# main.net
KiCad netlist of a schematic drawn in EAGLE
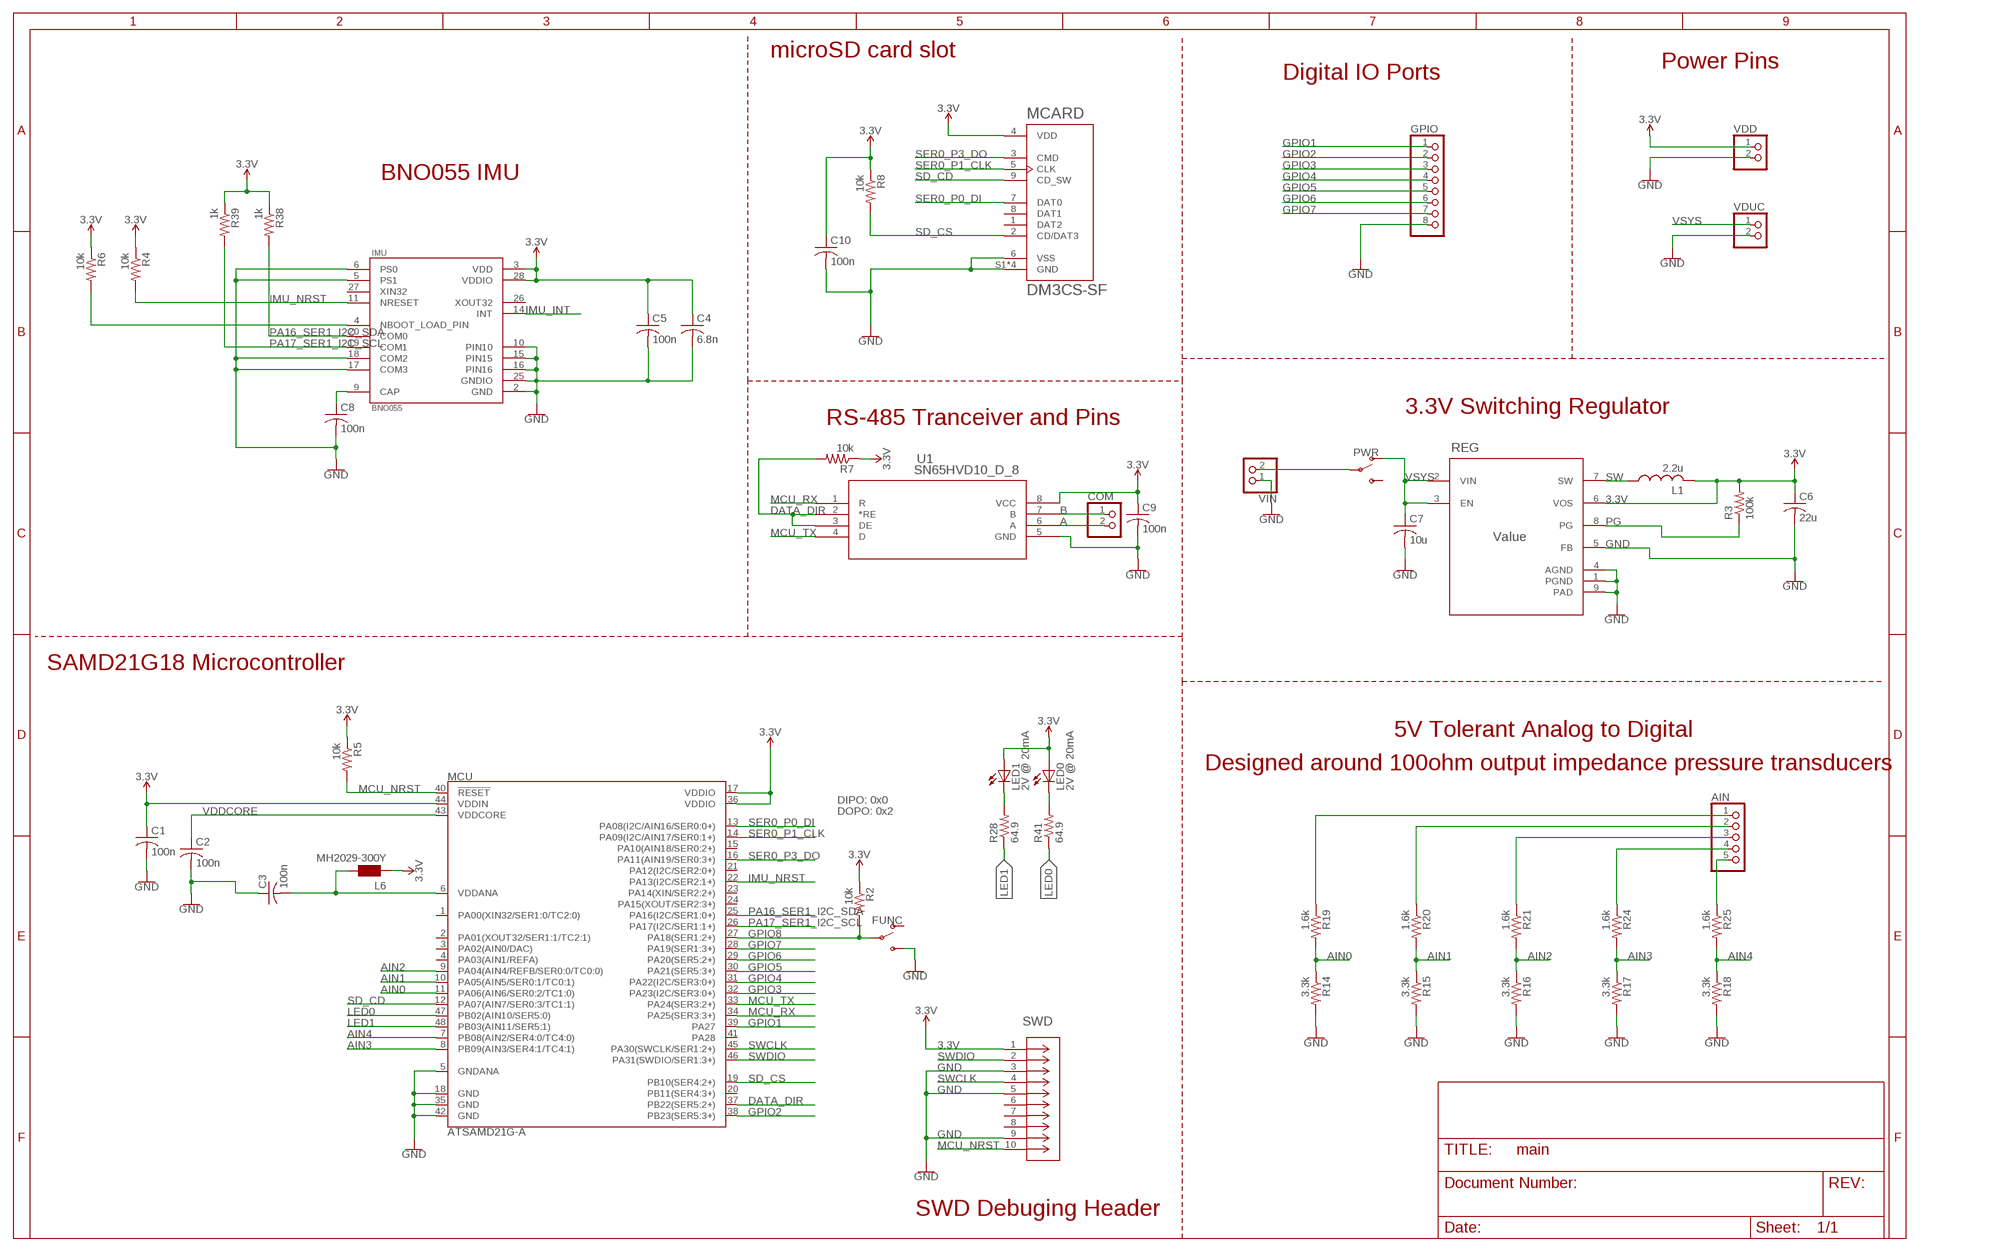
[diagram p0: schematic, sheet 1]

(export (version "E")
  (design (tool "Eeschema 10.0.6"))
  (components
    (comp (ref "AIN")
      (value "PINHD-1X5")
      (footprint "eagle-import:1X05")
      (libsource (lib "eagle-import") (part "PINHD-1X5"))
    )
    (comp (ref "C1")
      (value "100n")
      (footprint "eagle-import:C0603")
      (libsource (lib "eagle-import") (part "C-USC0603"))
    )
    (comp (ref "C2")
      (value "100n")
      (footprint "eagle-import:C0603")
      (libsource (lib "eagle-import") (part "C-USC0603"))
    )
    (comp (ref "C3")
      (value "100n")
      (footprint "eagle-import:C0603")
      (libsource (lib "eagle-import") (part "C-USC0603"))
    )
    (comp (ref "C4")
      (value "6.8n")
      (footprint "eagle-import:C0603")
      (libsource (lib "eagle-import") (part "C-USC0603"))
    )
    (comp (ref "C5")
      (value "100n")
      (footprint "eagle-import:C0603")
      (libsource (lib "eagle-import") (part "C-USC0603"))
    )
    (comp (ref "C6")
      (value "22u")
      (footprint "eagle-import:C0603")
      (libsource (lib "eagle-import") (part "C-USC0603"))
    )
    (comp (ref "C7")
      (value "10u")
      (footprint "eagle-import:C0603")
      (libsource (lib "eagle-import") (part "C-USC0603"))
    )
    (comp (ref "C8")
      (value "100n")
      (footprint "eagle-import:C0603")
      (libsource (lib "eagle-import") (part "C-USC0603"))
    )
    (comp (ref "C9")
      (value "100n")
      (footprint "eagle-import:C0603")
      (libsource (lib "eagle-import") (part "C-USC0603"))
    )
    (comp (ref "C10")
      (value "100n")
      (footprint "eagle-import:C0603")
      (libsource (lib "eagle-import") (part "C-USC0603"))
    )
    (comp (ref "COM")
      (value "PINHD-1X2")
      (footprint "eagle-import:1X02")
      (libsource (lib "eagle-import") (part "PINHD-1X2"))
    )
    (comp (ref "FUNC")
      (value "SWITCH-SPDT-SMD-AYZ0202")
      (footprint "eagle-import:SWITCH_DPDT_SMD_AYZ0202")
      (libsource (lib "eagle-import") (part "SWITCH-SPDT-SMD-AYZ0202"))
    )
    (comp (ref "GPIO")
      (value "PINHD-1X8")
      (footprint "eagle-import:1X08")
      (libsource (lib "eagle-import") (part "PINHD-1X8"))
    )
    (comp (ref "IMU")
      (value "BNO055")
      (footprint "eagle-import:LGA28R50P4X10_380X520X100")
      (fields (field (name "MF") "Bosch"))
      (libsource (lib "eagle-import") (part "BNO055"))
    )
    (comp (ref "L1")
      (value "2.2u")
      (footprint "eagle-import:L2012C")
      (libsource (lib "eagle-import") (part "L-USL2012C"))
    )
    (comp (ref "L6")
      (value "MH2029-300Y")
      (footprint "eagle-import:0805")
      (fields (field (name "PART_NUMBER") "BLM21PG300SN1D_/_MH2029-300Y"))
      (libsource (lib "eagle-import") (part "0001_BLM21PG300SN1D_/_MH2029-300Y"))
    )
    (comp (ref "LED0")
      (value "2V @ 20mA")
      (footprint "eagle-import:CHIPLED_0603")
      (libsource (lib "eagle-import") (part "LEDCHIPLED_0603"))
    )
    (comp (ref "LED1")
      (value "2V @ 20mA")
      (footprint "eagle-import:CHIPLED_0603")
      (libsource (lib "eagle-import") (part "LEDCHIPLED_0603"))
    )
    (comp (ref "MCARD")
      (value "DM3CS-SF")
      (footprint "eagle-import:HRS_DM3CS-SF")
      (fields (field (name "DIGI-KEY_PART_NUMBER") "HR1972CT-ND") (field (name "MF") "Hirose"))
      (libsource (lib "eagle-import") (part "DM3CS-SF"))
    )
    (comp (ref "MCU")
      (value "ATSAMD21G-A")
      (footprint "eagle-import:TQFP-48")
      (libsource (lib "eagle-import") (part "ATSAMD21G-A"))
    )
    (comp (ref "PWR")
      (value "SWITCH-SPDT-PTH-11.6X4.0MM")
      (footprint "eagle-import:SWITCH_SPDT_PTH_11.6X4.0MM")
      (libsource (lib "eagle-import") (part "SWITCH-SPDT-PTH-11.6X4.0MM"))
    )
    (comp (ref "R2")
      (value "10k")
      (footprint "eagle-import:R0603")
      (libsource (lib "eagle-import") (part "R-US_R0603"))
    )
    (comp (ref "R3")
      (value "100k")
      (footprint "eagle-import:R0603")
      (libsource (lib "eagle-import") (part "R-US_R0603"))
    )
    (comp (ref "R4")
      (value "10k")
      (footprint "eagle-import:R0603")
      (libsource (lib "eagle-import") (part "R-US_R0603"))
    )
    (comp (ref "R5")
      (value "10k")
      (footprint "eagle-import:R0603")
      (libsource (lib "eagle-import") (part "R-US_R0603"))
    )
    (comp (ref "R6")
      (value "10k")
      (footprint "eagle-import:R0603")
      (libsource (lib "eagle-import") (part "R-US_R0603"))
    )
    (comp (ref "R7")
      (value "10k")
      (footprint "eagle-import:R0603")
      (libsource (lib "eagle-import") (part "R-US_R0603"))
    )
    (comp (ref "R8")
      (value "10k")
      (footprint "eagle-import:R0603")
      (libsource (lib "eagle-import") (part "R-US_R0603"))
    )
    (comp (ref "R14")
      (value "3.3k")
      (footprint "eagle-import:R0603")
      (libsource (lib "eagle-import") (part "R-US_R0603"))
    )
    (comp (ref "R15")
      (value "3.3k")
      (footprint "eagle-import:R0603")
      (libsource (lib "eagle-import") (part "R-US_R0603"))
    )
    (comp (ref "R16")
      (value "3.3k")
      (footprint "eagle-import:R0603")
      (libsource (lib "eagle-import") (part "R-US_R0603"))
    )
    (comp (ref "R17")
      (value "3.3k")
      (footprint "eagle-import:R0603")
      (libsource (lib "eagle-import") (part "R-US_R0603"))
    )
    (comp (ref "R18")
      (value "3.3k")
      (footprint "eagle-import:R0603")
      (libsource (lib "eagle-import") (part "R-US_R0603"))
    )
    (comp (ref "R19")
      (value "1.6k")
      (footprint "eagle-import:R0603")
      (libsource (lib "eagle-import") (part "R-US_R0603"))
    )
    (comp (ref "R20")
      (value "1.6k")
      (footprint "eagle-import:R0603")
      (libsource (lib "eagle-import") (part "R-US_R0603"))
    )
    (comp (ref "R21")
      (value "1.6k")
      (footprint "eagle-import:R0603")
      (libsource (lib "eagle-import") (part "R-US_R0603"))
    )
    (comp (ref "R24")
      (value "1.6k")
      (footprint "eagle-import:R0603")
      (libsource (lib "eagle-import") (part "R-US_R0603"))
    )
    (comp (ref "R25")
      (value "1.6k")
      (footprint "eagle-import:R0603")
      (libsource (lib "eagle-import") (part "R-US_R0603"))
    )
    (comp (ref "R28")
      (value "64.9")
      (footprint "eagle-import:R0603")
      (libsource (lib "eagle-import") (part "R-US_R0603"))
    )
    (comp (ref "R38")
      (value "1k")
      (footprint "eagle-import:R0603")
      (libsource (lib "eagle-import") (part "R-US_R0603"))
    )
    (comp (ref "R39")
      (value "1k")
      (footprint "eagle-import:R0603")
      (libsource (lib "eagle-import") (part "R-US_R0603"))
    )
    (comp (ref "R41")
      (value "64.9")
      (footprint "eagle-import:R0603")
      (libsource (lib "eagle-import") (part "R-US_R0603"))
    )
    (comp (ref "REG")
      (value "Value")
      (footprint "eagle-import:DSG0008A")
      (fields (field (name "MANUFACTURER") "Texas Instruments") (field (name "PARTNUMBER") "TPS62162QDSGRQ1"))
      (libsource (lib "eagle-import") (part "TPS62162QDSGRQ1"))
    )
    (comp (ref "SWD")
      (value "DEBUG-HEADER")
      (footprint "eagle-import:CONN_MINITEK_2X5_HDR")
      (fields (field (name "MANUFACTURER_PART_NUMBER") "2002111100010T4LF"))
      (libsource (lib "eagle-import") (part "DEBUG-HEADER"))
    )
    (comp (ref "U1")
      (value "SN65HVD10_D_8")
      (footprint "eagle-import:D8")
      (fields
        (field (name "GENERIC_PART_NUMBER") "SN65HVD10")
        (field (name "MANUFACTURER") "Texas Instruments")
        (field (name "MANUFACTURER_PART_NUMBER") "sn65hvd10_d_8")
      )
      (libsource (lib "eagle-import") (part "SN65HVD10_D_8"))
    )
    (comp (ref "VDD")
      (value "PINHD-1X2")
      (footprint "eagle-import:1X02")
      (libsource (lib "eagle-import") (part "PINHD-1X2"))
    )
    (comp (ref "VDUC")
      (value "PINHD-1X2")
      (footprint "eagle-import:1X02")
      (libsource (lib "eagle-import") (part "PINHD-1X2"))
    )
    (comp (ref "VIN")
      (value "PINHD-1X2")
      (footprint "eagle-import:1X02")
      (libsource (lib "eagle-import") (part "PINHD-1X2"))
    )
  )
  (nets
    (net (code "1") (name "/A") (class "Default")
      (node (ref "COM") (pin "2") (pinfunction "2_2") (pintype "passive"))
      (node (ref "U1") (pin "6") (pinfunction "A_6") (pintype "input"))
    )
    (net (code "2") (name "/AIN0") (class "Default")
      (node (ref "MCU") (pin "11") (pinfunction "PA06(AIN6/SER0:2/TC1:0)_11") (pintype "bidirectional"))
      (node (ref "R14") (pin "1") (pinfunction "1_1") (pintype "passive"))
      (node (ref "R19") (pin "2") (pinfunction "2_2") (pintype "passive"))
    )
    (net (code "3") (name "/AIN1") (class "Default")
      (node (ref "MCU") (pin "10") (pinfunction "PA05(AIN5/SER0:1/TC0:1)_10") (pintype "bidirectional"))
      (node (ref "R15") (pin "1") (pinfunction "1_1") (pintype "passive"))
      (node (ref "R20") (pin "2") (pinfunction "2_2") (pintype "passive"))
    )
    (net (code "4") (name "/AIN2") (class "Default")
      (node (ref "MCU") (pin "9") (pinfunction "PA04(AIN4/REFB/SER0:0/TC0:0)_9") (pintype "bidirectional"))
      (node (ref "R16") (pin "1") (pinfunction "1_1") (pintype "passive"))
      (node (ref "R21") (pin "2") (pinfunction "2_2") (pintype "passive"))
    )
    (net (code "5") (name "/AIN3") (class "Default")
      (node (ref "MCU") (pin "8") (pinfunction "PB09(AIN3/SER4:1/TC4:1)_8") (pintype "bidirectional"))
      (node (ref "R17") (pin "1") (pinfunction "1_1") (pintype "passive"))
      (node (ref "R24") (pin "2") (pinfunction "2_2") (pintype "passive"))
    )
    (net (code "6") (name "/AIN4") (class "Default")
      (node (ref "MCU") (pin "7") (pinfunction "PB08(AIN2/SER4:0/TC4:0)_7") (pintype "bidirectional"))
      (node (ref "R18") (pin "1") (pinfunction "1_1") (pintype "passive"))
      (node (ref "R25") (pin "2") (pinfunction "2_2") (pintype "passive"))
    )
    (net (code "7") (name "/B") (class "Default")
      (node (ref "COM") (pin "1") (pinfunction "1_1") (pintype "passive"))
      (node (ref "U1") (pin "7") (pinfunction "B_7") (pintype "input"))
    )
    (net (code "8") (name "/DATA_DIR") (class "Default")
      (node (ref "MCU") (pin "37") (pinfunction "PB22(SER5:2+)_37") (pintype "bidirectional"))
      (node (ref "R7") (pin "2") (pinfunction "2_2") (pintype "passive"))
      (node (ref "U1") (pin "2") (pinfunction "*RE_2") (pintype "input"))
      (node (ref "U1") (pin "3") (pinfunction "DE_3") (pintype "input"))
    )
    (net (code "9") (name "/GPIO1") (class "Default")
      (node (ref "GPIO") (pin "1") (pinfunction "1_1") (pintype "passive"))
      (node (ref "MCU") (pin "39") (pinfunction "PA27_39") (pintype "bidirectional"))
    )
    (net (code "10") (name "/GPIO2") (class "Default")
      (node (ref "GPIO") (pin "2") (pinfunction "2_2") (pintype "passive"))
      (node (ref "MCU") (pin "38") (pinfunction "PB23(SER5:3+)_38") (pintype "bidirectional"))
    )
    (net (code "11") (name "/GPIO3") (class "Default")
      (node (ref "GPIO") (pin "3") (pinfunction "3_3") (pintype "passive"))
      (node (ref "MCU") (pin "32") (pinfunction "PA23(I2C/SER3:0+)_32") (pintype "bidirectional"))
    )
    (net (code "12") (name "/GPIO4") (class "Default")
      (node (ref "GPIO") (pin "4") (pinfunction "4_4") (pintype "passive"))
      (node (ref "MCU") (pin "31") (pinfunction "PA22(I2C/SER3:0+)_31") (pintype "bidirectional"))
    )
    (net (code "13") (name "/GPIO5") (class "Default")
      (node (ref "GPIO") (pin "5") (pinfunction "5_5") (pintype "passive"))
      (node (ref "MCU") (pin "30") (pinfunction "PA21(SER5:3+)_30") (pintype "bidirectional"))
    )
    (net (code "14") (name "/GPIO6") (class "Default")
      (node (ref "GPIO") (pin "6") (pinfunction "6_6") (pintype "passive"))
      (node (ref "MCU") (pin "29") (pinfunction "PA20(SER5:2+)_29") (pintype "bidirectional"))
    )
    (net (code "15") (name "/GPIO7") (class "Default")
      (node (ref "GPIO") (pin "7") (pinfunction "7_7") (pintype "passive"))
      (node (ref "MCU") (pin "28") (pinfunction "PA19(SER1:3+)_28") (pintype "bidirectional"))
    )
    (net (code "16") (name "/GPIO8") (class "Default")
      (node (ref "FUNC") (pin "2") (pinfunction "P_2") (pintype "passive"))
      (node (ref "MCU") (pin "27") (pinfunction "PA18(SER1:2+)_27") (pintype "bidirectional"))
      (node (ref "R2") (pin "2") (pinfunction "2_2") (pintype "passive"))
    )
    (net (code "17") (name "/IMU_INT") (class "Default")
      (node (ref "IMU") (pin "14") (pinfunction "INT_14") (pintype "output"))
    )
    (net (code "18") (name "/IMU_NRST") (class "Default")
      (node (ref "IMU") (pin "11") (pinfunction "NRESET_11") (pintype "input"))
      (node (ref "MCU") (pin "22") (pinfunction "PA13(I2C/SER2:1+)_22") (pintype "bidirectional"))
      (node (ref "R4") (pin "2") (pinfunction "2_2") (pintype "passive"))
    )
    (net (code "19") (name "/MCU_NRST") (class "Default")
      (node (ref "MCU") (pin "40") (pinfunction "~{RESET}_40") (pintype "bidirectional"))
      (node (ref "R5") (pin "2") (pinfunction "2_2") (pintype "passive"))
      (node (ref "SWD") (pin "10") (pinfunction "10_10") (pintype "passive"))
    )
    (net (code "20") (name "/MCU_RX") (class "Default")
      (node (ref "MCU") (pin "34") (pinfunction "PA25(SER3:3+)_34") (pintype "bidirectional"))
      (node (ref "U1") (pin "1") (pinfunction "R_1") (pintype "input"))
    )
    (net (code "21") (name "/MCU_TX") (class "Default")
      (node (ref "MCU") (pin "33") (pinfunction "PA24(SER3:2+)_33") (pintype "bidirectional"))
      (node (ref "U1") (pin "4") (pinfunction "D_4") (pintype "input"))
    )
    (net (code "22") (name "/PA16_SER1_I2C_SDA") (class "Default")
      (node (ref "IMU") (pin "20") (pinfunction "COM0_20") (pintype "bidirectional"))
      (node (ref "MCU") (pin "25") (pinfunction "PA16(I2C/SER1:0+)_25") (pintype "bidirectional"))
      (node (ref "R38") (pin "2") (pinfunction "2_2") (pintype "passive"))
    )
    (net (code "23") (name "/PA17_SER1_I2C_SCL") (class "Default")
      (node (ref "IMU") (pin "19") (pinfunction "COM1_19") (pintype "bidirectional"))
      (node (ref "MCU") (pin "26") (pinfunction "PA17(I2C/SER1:1+)_26") (pintype "bidirectional"))
      (node (ref "R39") (pin "2") (pinfunction "2_2") (pintype "passive"))
    )
    (net (code "24") (name "/PG") (class "Default")
      (node (ref "R3") (pin "1") (pinfunction "1_1") (pintype "passive"))
      (node (ref "REG") (pin "8") (pinfunction "PG_8") (pintype "tri_state"))
    )
    (net (code "25") (name "/SD_CD") (class "Default")
      (node (ref "MCARD") (pin "9") (pinfunction "CD_SW_9") (pintype "passive"))
      (node (ref "MCU") (pin "12") (pinfunction "PA07(AIN7/SER0:3/TC1:1)_12") (pintype "bidirectional"))
    )
    (net (code "26") (name "/SD_CS") (class "Default")
      (node (ref "MCARD") (pin "2") (pinfunction "CD/DAT3_2") (pintype "passive"))
      (node (ref "MCU") (pin "19") (pinfunction "PB10(SER4:2+)_19") (pintype "bidirectional"))
      (node (ref "R8") (pin "2") (pinfunction "2_2") (pintype "passive"))
    )
    (net (code "27") (name "/SER0_P0_DI") (class "Default")
      (node (ref "MCARD") (pin "7") (pinfunction "DAT0_7") (pintype "passive"))
      (node (ref "MCU") (pin "13") (pinfunction "PA08(I2C/AIN16/SER0:0+)_13") (pintype "bidirectional"))
    )
    (net (code "28") (name "/SER0_P1_CLK") (class "Default")
      (node (ref "MCARD") (pin "5") (pinfunction "CLK_5") (pintype "passive"))
      (node (ref "MCU") (pin "14") (pinfunction "PA09(I2C/AIN17/SER0:1+)_14") (pintype "bidirectional"))
    )
    (net (code "29") (name "/SER0_P3_DO") (class "Default")
      (node (ref "MCARD") (pin "3") (pinfunction "CMD_3") (pintype "passive"))
      (node (ref "MCU") (pin "16") (pinfunction "PA11(AIN19/SER0:3+)_16") (pintype "bidirectional"))
    )
    (net (code "30") (name "/SW") (class "Default")
      (node (ref "L1") (pin "1") (pinfunction "1_1") (pintype "passive"))
      (node (ref "REG") (pin "7") (pinfunction "SW_7") (pintype "power_in"))
    )
    (net (code "31") (name "/SWCLK") (class "Default")
      (node (ref "MCU") (pin "45") (pinfunction "PA30(SWCLK/SER1:2+)_45") (pintype "bidirectional"))
      (node (ref "SWD") (pin "4") (pinfunction "4_4") (pintype "passive"))
    )
    (net (code "32") (name "/SWDIO") (class "Default")
      (node (ref "MCU") (pin "46") (pinfunction "PA31(SWDIO/SER1:3+)_46") (pintype "bidirectional"))
      (node (ref "SWD") (pin "2") (pinfunction "2_2") (pintype "passive"))
    )
    (net (code "33") (name "/VDDCORE") (class "Default")
      (node (ref "C2") (pin "1") (pinfunction "1_1") (pintype "passive"))
      (node (ref "MCU") (pin "43") (pinfunction "VDDCORE_43") (pintype "bidirectional"))
    )
    (net (code "34") (name "/VSYS") (class "Default")
      (node (ref "C7") (pin "1") (pinfunction "1_1") (pintype "passive"))
      (node (ref "PWR") (pin "1") (pinfunction "O_1") (pintype "passive"))
      (node (ref "REG") (pin "2") (pinfunction "VIN_2") (pintype "power_in"))
      (node (ref "REG") (pin "3") (pinfunction "EN_3") (pintype "input"))
      (node (ref "VDUC") (pin "1") (pinfunction "1_1") (pintype "passive"))
    )
    (net (code "35") (name "3.3V") (class "Default")
      (node (ref "C1") (pin "1") (pinfunction "1_1") (pintype "passive"))
      (node (ref "C10") (pin "1") (pinfunction "1_1") (pintype "passive"))
      (node (ref "C4") (pin "1") (pinfunction "1_1") (pintype "passive"))
      (node (ref "C5") (pin "1") (pinfunction "1_1") (pintype "passive"))
      (node (ref "C6") (pin "1") (pinfunction "1_1") (pintype "passive"))
      (node (ref "C9") (pin "1") (pinfunction "1_1") (pintype "passive"))
      (node (ref "IMU") (pin "28") (pinfunction "VDDIO_28") (pintype "power_in"))
      (node (ref "IMU") (pin "3") (pinfunction "VDD_3") (pintype "power_in"))
      (node (ref "L1") (pin "2") (pinfunction "2_2") (pintype "passive"))
      (node (ref "L6") (pin "1") (pinfunction "1_1") (pintype "passive"))
      (node (ref "LED0") (pin "A") (pinfunction "A_A") (pintype "passive"))
      (node (ref "LED1") (pin "A") (pinfunction "A_A") (pintype "passive"))
      (node (ref "MCARD") (pin "4") (pinfunction "VDD_4") (pintype "passive"))
      (node (ref "MCU") (pin "17") (pinfunction "VDDIO_17") (pintype "bidirectional"))
      (node (ref "MCU") (pin "36") (pinfunction "VDDIO_36") (pintype "bidirectional"))
      (node (ref "MCU") (pin "44") (pinfunction "VDDIN_44") (pintype "bidirectional"))
      (node (ref "R2") (pin "1") (pinfunction "1_1") (pintype "passive"))
      (node (ref "R3") (pin "2") (pinfunction "2_2") (pintype "passive"))
      (node (ref "R38") (pin "1") (pinfunction "1_1") (pintype "passive"))
      (node (ref "R39") (pin "1") (pinfunction "1_1") (pintype "passive"))
      (node (ref "R4") (pin "1") (pinfunction "1_1") (pintype "passive"))
      (node (ref "R5") (pin "1") (pinfunction "1_1") (pintype "passive"))
      (node (ref "R6") (pin "1") (pinfunction "1_1") (pintype "passive"))
      (node (ref "R7") (pin "1") (pinfunction "1_1") (pintype "passive"))
      (node (ref "R8") (pin "1") (pinfunction "1_1") (pintype "passive"))
      (node (ref "REG") (pin "6") (pinfunction "VOS_6") (pintype "input"))
      (node (ref "SWD") (pin "1") (pinfunction "1_1") (pintype "passive"))
      (node (ref "U1") (pin "8") (pinfunction "VCC_8") (pintype "power_in"))
      (node (ref "VDD") (pin "1") (pinfunction "1_1") (pintype "passive"))
    )
    (net (code "36") (name "GND") (class "Default")
      (node (ref "C1") (pin "2") (pinfunction "2_2") (pintype "passive"))
      (node (ref "C10") (pin "2") (pinfunction "2_2") (pintype "passive"))
      (node (ref "C2") (pin "2") (pinfunction "2_2") (pintype "passive"))
      (node (ref "C3") (pin "1") (pinfunction "1_1") (pintype "passive"))
      (node (ref "C4") (pin "2") (pinfunction "2_2") (pintype "passive"))
      (node (ref "C5") (pin "2") (pinfunction "2_2") (pintype "passive"))
      (node (ref "C6") (pin "2") (pinfunction "2_2") (pintype "passive"))
      (node (ref "C7") (pin "2") (pinfunction "2_2") (pintype "passive"))
      (node (ref "C8") (pin "2") (pinfunction "2_2") (pintype "passive"))
      (node (ref "C9") (pin "2") (pinfunction "2_2") (pintype "passive"))
      (node (ref "FUNC") (pin "3") (pinfunction "S_3") (pintype "passive"))
      (node (ref "GPIO") (pin "8") (pinfunction "8_8") (pintype "passive"))
      (node (ref "IMU") (pin "10") (pinfunction "PIN10_10") (pintype "power_in"))
      (node (ref "IMU") (pin "15") (pinfunction "PIN15_15") (pintype "power_in"))
      (node (ref "IMU") (pin "16") (pinfunction "PIN16_16") (pintype "power_in"))
      (node (ref "IMU") (pin "17") (pinfunction "COM3_17") (pintype "bidirectional"))
      (node (ref "IMU") (pin "18") (pinfunction "COM2_18") (pintype "bidirectional"))
      (node (ref "IMU") (pin "2") (pinfunction "GND_2") (pintype "power_in"))
      (node (ref "IMU") (pin "25") (pinfunction "GNDIO_25") (pintype "power_in"))
      (node (ref "IMU") (pin "5") (pinfunction "PS1_5") (pintype "input"))
      (node (ref "IMU") (pin "6") (pinfunction "PS0_6") (pintype "input"))
      (node (ref "MCARD") (pin "6") (pinfunction "VSS_6") (pintype "passive"))
      (node (ref "MCARD") (pin "S1") (pinfunction "GND_S1") (pintype "passive"))
      (node (ref "MCARD") (pin "S2") (pinfunction "GND_S2") (pintype "passive"))
      (node (ref "MCARD") (pin "S3") (pinfunction "GND_S3") (pintype "passive"))
      (node (ref "MCARD") (pin "S5") (pinfunction "GND_S5") (pintype "passive"))
      (node (ref "MCU") (pin "18") (pinfunction "GND_18") (pintype "bidirectional"))
      (node (ref "MCU") (pin "35") (pinfunction "GND_35") (pintype "bidirectional"))
      (node (ref "MCU") (pin "42") (pinfunction "GND_42") (pintype "bidirectional"))
      (node (ref "MCU") (pin "5") (pinfunction "GNDANA_5") (pintype "bidirectional"))
      (node (ref "R14") (pin "2") (pinfunction "2_2") (pintype "passive"))
      (node (ref "R15") (pin "2") (pinfunction "2_2") (pintype "passive"))
      (node (ref "R16") (pin "2") (pinfunction "2_2") (pintype "passive"))
      (node (ref "R17") (pin "2") (pinfunction "2_2") (pintype "passive"))
      (node (ref "R18") (pin "2") (pinfunction "2_2") (pintype "passive"))
      (node (ref "REG") (pin "1") (pinfunction "PGND_1") (pintype "power_in"))
      (node (ref "REG") (pin "4") (pinfunction "AGND_4") (pintype "power_in"))
      (node (ref "REG") (pin "5") (pinfunction "FB_5") (pintype "input"))
      (node (ref "REG") (pin "9") (pinfunction "PAD_9") (pintype "power_in"))
      (node (ref "SWD") (pin "3") (pinfunction "3_3") (pintype "passive"))
      (node (ref "SWD") (pin "5") (pinfunction "5_5") (pintype "passive"))
      (node (ref "SWD") (pin "9") (pinfunction "9_9") (pintype "passive"))
      (node (ref "U1") (pin "5") (pinfunction "GND_5") (pintype "power_in"))
      (node (ref "VDD") (pin "2") (pinfunction "2_2") (pintype "passive"))
      (node (ref "VDUC") (pin "2") (pinfunction "2_2") (pintype "passive"))
      (node (ref "VIN") (pin "1") (pinfunction "1_1") (pintype "passive"))
    )
    (net (code "37") (name "LED0") (class "Default")
      (node (ref "MCU") (pin "47") (pinfunction "PB02(AIN10/SER5:0)_47") (pintype "bidirectional"))
      (node (ref "R41") (pin "1") (pinfunction "1_1") (pintype "passive"))
    )
    (net (code "38") (name "LED1") (class "Default")
      (node (ref "MCU") (pin "48") (pinfunction "PB03(AIN11/SER5:1)_48") (pintype "bidirectional"))
      (node (ref "R28") (pin "1") (pinfunction "1_1") (pintype "passive"))
    )
    (net (code "39") (name "Net-(AIN-Pad1)") (class "Default")
      (node (ref "AIN") (pin "1") (pinfunction "1_1") (pintype "passive"))
      (node (ref "R19") (pin "1") (pinfunction "1_1") (pintype "passive"))
    )
    (net (code "40") (name "Net-(AIN-Pad2)") (class "Default")
      (node (ref "AIN") (pin "2") (pinfunction "2_2") (pintype "passive"))
      (node (ref "R20") (pin "1") (pinfunction "1_1") (pintype "passive"))
    )
    (net (code "41") (name "Net-(AIN-Pad3)") (class "Default")
      (node (ref "AIN") (pin "3") (pinfunction "3_3") (pintype "passive"))
      (node (ref "R21") (pin "1") (pinfunction "1_1") (pintype "passive"))
    )
    (net (code "42") (name "Net-(AIN-Pad4)") (class "Default")
      (node (ref "AIN") (pin "4") (pinfunction "4_4") (pintype "passive"))
      (node (ref "R24") (pin "1") (pinfunction "1_1") (pintype "passive"))
    )
    (net (code "43") (name "Net-(AIN-Pad5)") (class "Default")
      (node (ref "AIN") (pin "5") (pinfunction "5_5") (pintype "passive"))
      (node (ref "R25") (pin "1") (pinfunction "1_1") (pintype "passive"))
    )
    (net (code "44") (name "Net-(IMU-CAP)") (class "Default")
      (node (ref "C8") (pin "1") (pinfunction "1_1") (pintype "passive"))
      (node (ref "IMU") (pin "9") (pinfunction "CAP_9") (pintype "passive"))
    )
    (net (code "45") (name "Net-(IMU-NBOOT_LOAD_PIN)") (class "Default")
      (node (ref "IMU") (pin "4") (pinfunction "NBOOT_LOAD_PIN_4") (pintype "bidirectional"))
      (node (ref "R6") (pin "2") (pinfunction "2_2") (pintype "passive"))
    )
    (net (code "46") (name "Net-(LED0-PadC)") (class "Default")
      (node (ref "LED0") (pin "C") (pinfunction "C_C") (pintype "passive"))
      (node (ref "R41") (pin "2") (pinfunction "2_2") (pintype "passive"))
    )
    (net (code "47") (name "Net-(LED1-PadC)") (class "Default")
      (node (ref "LED1") (pin "C") (pinfunction "C_C") (pintype "passive"))
      (node (ref "R28") (pin "2") (pinfunction "2_2") (pintype "passive"))
    )
    (net (code "48") (name "Net-(MCU-VDDANA)") (class "Default")
      (node (ref "C3") (pin "2") (pinfunction "2_2") (pintype "passive"))
      (node (ref "L6") (pin "2") (pinfunction "2_2") (pintype "passive"))
      (node (ref "MCU") (pin "6") (pinfunction "VDDANA_6") (pintype "bidirectional"))
    )
    (net (code "49") (name "Net-(PWR-P)") (class "Default")
      (node (ref "PWR") (pin "2") (pinfunction "P_2") (pintype "passive"))
      (node (ref "VIN") (pin "2") (pinfunction "2_2") (pintype "passive"))
    )
    (net (code "50") (name "unconnected-(FUNC-O-Pad1)") (class "Default")
      (node (ref "FUNC") (pin "1") (pinfunction "O_1") (pintype "passive"))
    )
    (net (code "51") (name "unconnected-(IMU-XIN32-Pad27)") (class "Default")
      (node (ref "IMU") (pin "27") (pinfunction "XIN32_27") (pintype "input"))
    )
    (net (code "52") (name "unconnected-(IMU-XOUT32-Pad26)") (class "Default")
      (node (ref "IMU") (pin "26") (pinfunction "XOUT32_26") (pintype "output"))
    )
    (net (code "53") (name "unconnected-(MCARD-DAT1-Pad8)") (class "Default")
      (node (ref "MCARD") (pin "8") (pinfunction "DAT1_8") (pintype "passive"))
    )
    (net (code "54") (name "unconnected-(MCARD-DAT2-Pad1)") (class "Default")
      (node (ref "MCARD") (pin "1") (pinfunction "DAT2_1") (pintype "passive"))
    )
    (net (code "55") (name "unconnected-(MCU-PA00(XIN32{slash}SER1:0{slash}TC2:0)-Pad1)") (class "Default")
      (node (ref "MCU") (pin "1") (pinfunction "PA00(XIN32/SER1:0/TC2:0)_1") (pintype "bidirectional"))
    )
    (net (code "56") (name "unconnected-(MCU-PA01(XOUT32{slash}SER1:1{slash}TC2:1)-Pad2)") (class "Default")
      (node (ref "MCU") (pin "2") (pinfunction "PA01(XOUT32/SER1:1/TC2:1)_2") (pintype "bidirectional"))
    )
    (net (code "57") (name "unconnected-(MCU-PA02(AIN0{slash}DAC)-Pad3)") (class "Default")
      (node (ref "MCU") (pin "3") (pinfunction "PA02(AIN0/DAC)_3") (pintype "bidirectional"))
    )
    (net (code "58") (name "unconnected-(MCU-PA03(AIN1{slash}REFA)-Pad4)") (class "Default")
      (node (ref "MCU") (pin "4") (pinfunction "PA03(AIN1/REFA)_4") (pintype "bidirectional"))
    )
    (net (code "59") (name "unconnected-(MCU-PA10(AIN18{slash}SER0:2+)-Pad15)") (class "Default")
      (node (ref "MCU") (pin "15") (pinfunction "PA10(AIN18/SER0:2+)_15") (pintype "bidirectional"))
    )
    (net (code "60") (name "unconnected-(MCU-PA12(I2C{slash}SER2:0+)-Pad21)") (class "Default")
      (node (ref "MCU") (pin "21") (pinfunction "PA12(I2C/SER2:0+)_21") (pintype "bidirectional"))
    )
    (net (code "61") (name "unconnected-(MCU-PA14(XIN{slash}SER2:2+)-Pad23)") (class "Default")
      (node (ref "MCU") (pin "23") (pinfunction "PA14(XIN/SER2:2+)_23") (pintype "bidirectional"))
    )
    (net (code "62") (name "unconnected-(MCU-PA15(XOUT{slash}SER2:3+)-Pad24)") (class "Default")
      (node (ref "MCU") (pin "24") (pinfunction "PA15(XOUT/SER2:3+)_24") (pintype "bidirectional"))
    )
    (net (code "63") (name "unconnected-(MCU-PA28-Pad41)") (class "Default")
      (node (ref "MCU") (pin "41") (pinfunction "PA28_41") (pintype "bidirectional"))
    )
    (net (code "64") (name "unconnected-(MCU-PB11(SER4:3+)-Pad20)") (class "Default")
      (node (ref "MCU") (pin "20") (pinfunction "PB11(SER4:3+)_20") (pintype "bidirectional"))
    )
    (net (code "65") (name "unconnected-(PWR-S-Pad3)") (class "Default")
      (node (ref "PWR") (pin "3") (pinfunction "S_3") (pintype "passive"))
    )
    (net (code "66") (name "unconnected-(SWD-Pad6)") (class "Default")
      (node (ref "SWD") (pin "6") (pinfunction "6_6") (pintype "passive"))
    )
    (net (code "67") (name "unconnected-(SWD-Pad7)") (class "Default")
      (node (ref "SWD") (pin "7") (pinfunction "7_7") (pintype "passive"))
    )
    (net (code "68") (name "unconnected-(SWD-Pad8)") (class "Default")
      (node (ref "SWD") (pin "8") (pinfunction "8_8") (pintype "passive"))
    )
  )
)
